# PIC16F87.net
KiCad netlist of a schematic drawn in Altium Designer
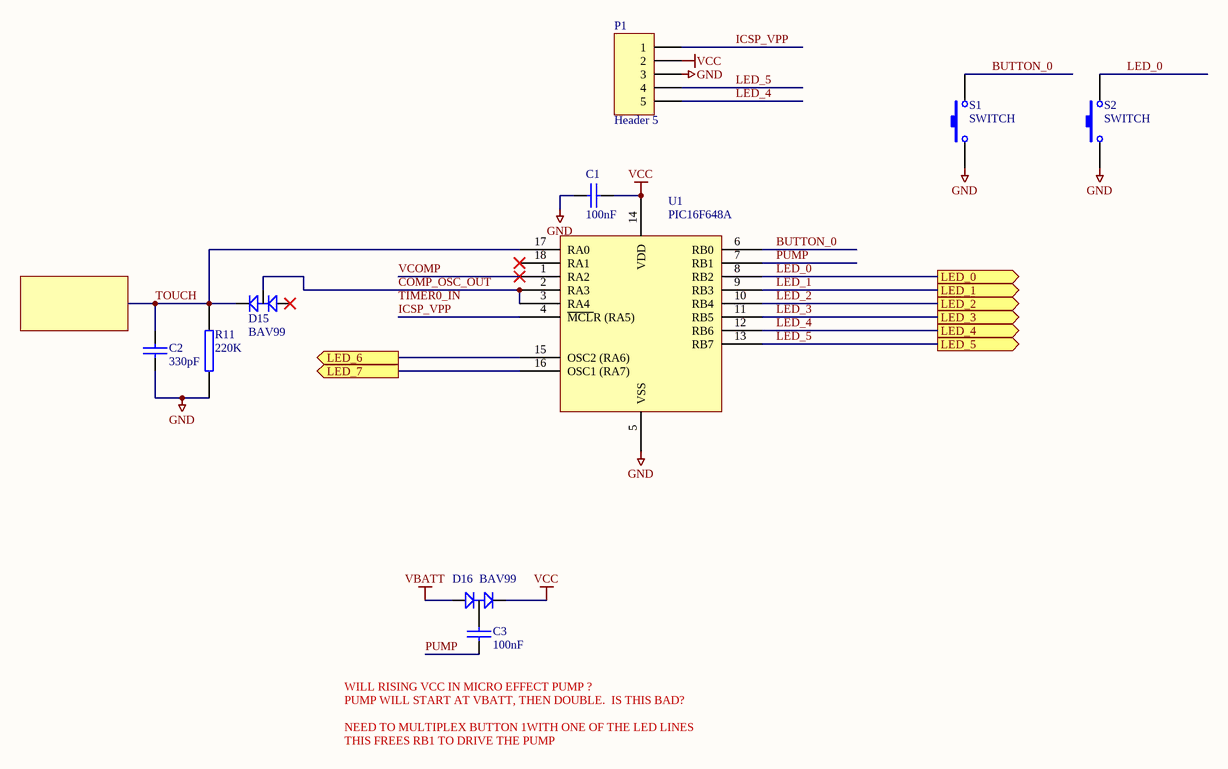
[diagram p0: PIC16F87.SchDoc]

(export (version "E")
  (design (tool "Eeschema 10.0.6"))
  (components
    (comp (ref "C1")
      (value "100nF")
      (footprint "CAP (3D) - 0603")
      (description "CAPACITOR SMD 0402")
      (libsource (lib "401 CCPA") (part "CAP"))
    )
    (comp (ref "C2")
      (value "330pF")
      (footprint "CAP (3D) - 0603")
      (description "CAPACITOR SMD 0402")
      (libsource (lib "401 CCPA") (part "CAP"))
    )
    (comp (ref "C3")
      (value "100nF")
      (footprint "CAP (3D) - 0603")
      (description "CAPACITOR SMD 0402")
      (libsource (lib "401 CCPA") (part "CAP"))
    )
    (comp (ref "D15")
      (value "BAV99")
      (footprint "SOT23-3L")
      (description "DUAL DIODE, BAV99")
      (fields (field (name "MOUSER PART NO.") "771-BAV99/T3") (field (name "FARNELL PART NO.") "9843612"))
      (libsource (lib "NASCO") (part "BAV99"))
    )
    (comp (ref "D16")
      (value "BAV99")
      (footprint "SOT23-3L")
      (description "DUAL DIODE, BAV99")
      (fields (field (name "MOUSER PART NO.") "771-BAV99/T3") (field (name "FARNELL PART NO.") "9843612"))
      (libsource (lib "NASCO") (part "BAV99"))
    )
    (comp (ref "P1")
      (value "Header 5")
      (footprint "HDR1X5")
      (description "Header, 5-Pin")
      (fields (field (name "PUBLISHER") "Altium Limited"))
      (libsource (lib "Miscellaneous Connectors") (part "Header 5"))
    )
    (comp (ref "R11")
      (value "220K")
      (footprint "RES (3D) - 0603")
      (description "ZERO OHM LINK")
      (libsource (lib "Mi-Call Schematic") (part "RES"))
    )
    (comp (ref "S1")
      (value "SWITCH")
      (footprint "TACT 6mm")
      (description "Switch")
      (fields (field (name "MOUSER PART NO.") "101-0264-EV") (field (name "MANUFACTURER") "Mountain Switch"))
      (libsource (lib "NASCO") (part "TACT SWITCH ALPS SKQMAQ"))
    )
    (comp (ref "S2")
      (value "SWITCH")
      (footprint "TACT 6mm")
      (description "Switch")
      (fields (field (name "MOUSER PART NO.") "101-0264-EV") (field (name "MANUFACTURER") "Mountain Switch"))
      (libsource (lib "NASCO") (part "TACT SWITCH ALPS SKQMAQ"))
    )
    (comp (ref "U1")
      (value "PIC16F648A")
      (footprint "SOIC-18")
      (description "PIC16F88")
      (fields
        (field (name "MOUSER PART NO.") "579-PIC16F88-E/SS")
        (field (name "FARNELL PART NO.") "9761519")
      )
      (libsource (lib "NASCO") (part "PIC16F87/88"))
    )
  )
  (nets
    (net (code "1") (name "/BUTTON_0") (class "Default")
      (node (ref "S1") (pin "2") (pinfunction "2_2") (pintype "passive"))
      (node (ref "U1") (pin "6") (pinfunction "RB0_6") (pintype "passive"))
    )
    (net (code "2") (name "/COMP_OSC_OUT") (class "Default")
      (node (ref "D15") (pin "3") (pinfunction "C1/A2_3") (pintype "passive"))
      (node (ref "U1") (pin "2") (pinfunction "RA3_2") (pintype "passive"))
      (node (ref "U1") (pin "3") (pinfunction "RA4_3") (pintype "passive"))
    )
    (net (code "3") (name "/ICSP_VPP") (class "Default")
      (node (ref "P1") (pin "1") (pinfunction "1_1") (pintype "passive"))
      (node (ref "U1") (pin "4") (pinfunction "~{MCL}R_(RA5)_4") (pintype "passive"))
    )
    (net (code "4") (name "/LED_0") (class "Default")
      (node (ref "S2") (pin "2") (pinfunction "2_2") (pintype "passive"))
      (node (ref "U1") (pin "8") (pinfunction "RB2_8") (pintype "passive"))
    )
    (net (code "5") (name "/LED_1") (class "Default")
      (node (ref "U1") (pin "9") (pinfunction "RB3_9") (pintype "passive"))
    )
    (net (code "6") (name "/LED_2") (class "Default")
      (node (ref "U1") (pin "10") (pinfunction "RB4_10") (pintype "passive"))
    )
    (net (code "7") (name "/LED_3") (class "Default")
      (node (ref "U1") (pin "11") (pinfunction "RB5_11") (pintype "passive"))
    )
    (net (code "8") (name "/LED_4") (class "Default")
      (node (ref "P1") (pin "5") (pinfunction "5_5") (pintype "passive"))
      (node (ref "U1") (pin "12") (pinfunction "RB6_12") (pintype "passive"))
    )
    (net (code "9") (name "/LED_5") (class "Default")
      (node (ref "P1") (pin "4") (pinfunction "4_4") (pintype "passive"))
      (node (ref "U1") (pin "13") (pinfunction "RB7_13") (pintype "passive"))
    )
    (net (code "10") (name "/LED_6") (class "Default")
      (node (ref "U1") (pin "15") (pinfunction "OSC2_(RA6)_15") (pintype "passive"))
    )
    (net (code "11") (name "/LED_7") (class "Default")
      (node (ref "U1") (pin "16") (pinfunction "OSC1_(RA7)_16") (pintype "passive"))
    )
    (net (code "12") (name "/PUMP") (class "Default")
      (node (ref "C3") (pin "2") (pinfunction "2_2") (pintype "passive"))
      (node (ref "U1") (pin "7") (pinfunction "RB1_7") (pintype "passive"))
    )
    (net (code "14") (name "/TOUCH") (class "Default")
      (node (ref "C2") (pin "1") (pinfunction "1_1") (pintype "passive"))
      (node (ref "D15") (pin "2") (pinfunction "C2_2") (pintype "passive"))
      (node (ref "R11") (pin "2") (pinfunction "2_2") (pintype "passive"))
      (node (ref "U1") (pin "17") (pinfunction "RA0_17") (pintype "passive"))
    )
    (net (code "15") (name "/VCOMP") (class "Default")
      (node (ref "U1") (pin "1") (pinfunction "RA2_1") (pintype "passive+no_connect"))
    )
    (net (code "16") (name "GND") (class "Default")
      (node (ref "C1") (pin "1") (pinfunction "1_1") (pintype "passive"))
      (node (ref "C2") (pin "2") (pinfunction "2_2") (pintype "passive"))
      (node (ref "P1") (pin "3") (pinfunction "3_3") (pintype "passive"))
      (node (ref "R11") (pin "1") (pinfunction "1_1") (pintype "passive"))
      (node (ref "S1") (pin "1") (pinfunction "1_1") (pintype "passive"))
      (node (ref "S2") (pin "1") (pinfunction "1_1") (pintype "passive"))
      (node (ref "U1") (pin "5") (pinfunction "VSS_5") (pintype "passive"))
    )
    (net (code "17") (name "Net-(D16-C1{slash}A2)") (class "Default")
      (node (ref "C3") (pin "1") (pinfunction "1_1") (pintype "passive"))
      (node (ref "D16") (pin "3") (pinfunction "C1/A2_3") (pintype "passive"))
    )
    (net (code "18") (name "VBATT") (class "Default")
      (node (ref "D16") (pin "1") (pinfunction "A1_1") (pintype "passive"))
    )
    (net (code "19") (name "VCC") (class "Default")
      (node (ref "C1") (pin "2") (pinfunction "2_2") (pintype "passive"))
      (node (ref "D16") (pin "2") (pinfunction "C2_2") (pintype "passive"))
      (node (ref "P1") (pin "2") (pinfunction "2_2") (pintype "passive"))
      (node (ref "U1") (pin "14") (pinfunction "VDD_14") (pintype "passive"))
    )
    (net (code "20") (name "unconnected-(D15-A1-Pad1)") (class "Default")
      (node (ref "D15") (pin "1") (pinfunction "A1_1") (pintype "passive+no_connect"))
    )
    (net (code "21") (name "unconnected-(U1-RA1-Pad18)") (class "Default")
      (node (ref "U1") (pin "18") (pinfunction "RA1_18") (pintype "passive+no_connect"))
    )
  )
)
